# M628A.net
KiCad netlist of a schematic drawn in EAGLE
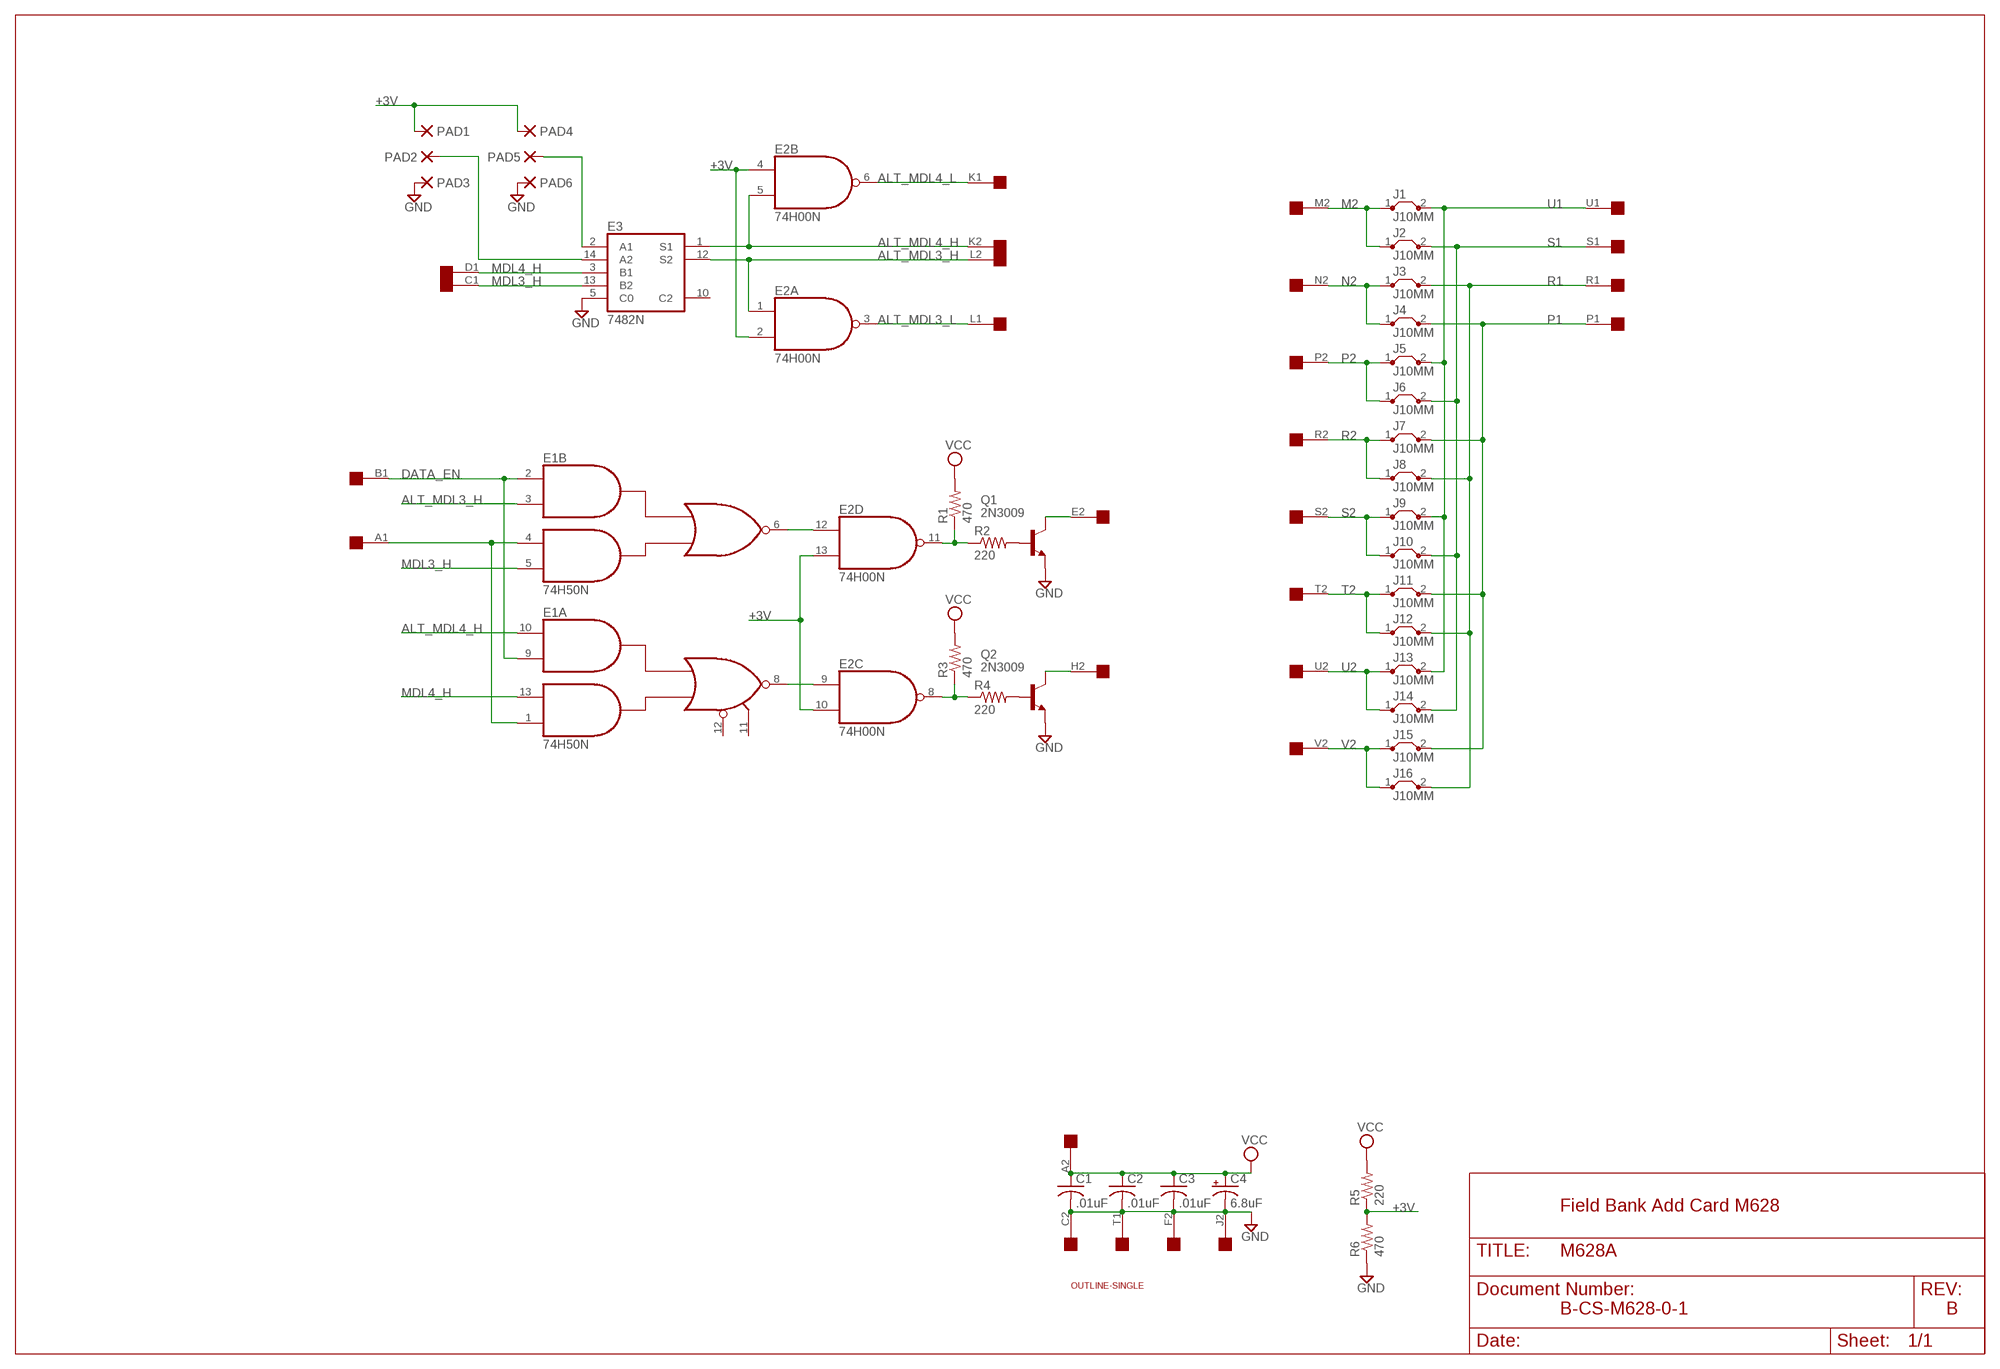
[diagram p0: schematic, sheet 1]

(export (version "E")
  (design (tool "Eeschema 10.0.6"))
  (components
    (comp (ref "C1")
      (value ".01uF")
      (footprint "eagle-import:C050-025X075")
      (libsource (lib "eagle-import") (part "C-US050-025X075"))
    )
    (comp (ref "C2")
      (value ".01uF")
      (footprint "eagle-import:C050-025X075")
      (libsource (lib "eagle-import") (part "C-US050-025X075"))
    )
    (comp (ref "C3")
      (value ".01uF")
      (footprint "eagle-import:C050-025X075")
      (libsource (lib "eagle-import") (part "C-US050-025X075"))
    )
    (comp (ref "C4")
      (value "6.8uF")
      (footprint "eagle-import:E12-8")
      (libsource (lib "eagle-import") (part "CPOL-USE20-8AXIAL"))
    )
    (comp (ref "E1")
      (value "74H50N")
      (footprint "eagle-import:DIL14")
      (libsource (lib "eagle-import") (part "7450N"))
    )
    (comp (ref "E2")
      (value "74H00N")
      (footprint "eagle-import:DIL14")
      (libsource (lib "eagle-import") (part "7400N"))
    )
    (comp (ref "E3")
      (value "7482N")
      (footprint "eagle-import:DIL14")
      (libsource (lib "eagle-import") (part "7482N"))
    )
    (comp (ref "J1")
      (value "J10MM")
      (footprint "eagle-import:10")
      (libsource (lib "eagle-import") (part "J10MM"))
    )
    (comp (ref "J2")
      (value "J10MM")
      (footprint "eagle-import:10")
      (libsource (lib "eagle-import") (part "J10MM"))
    )
    (comp (ref "J3")
      (value "J10MM")
      (footprint "eagle-import:10")
      (libsource (lib "eagle-import") (part "J10MM"))
    )
    (comp (ref "J4")
      (value "J10MM")
      (footprint "eagle-import:10")
      (libsource (lib "eagle-import") (part "J10MM"))
    )
    (comp (ref "J5")
      (value "J10MM")
      (footprint "eagle-import:10")
      (libsource (lib "eagle-import") (part "J10MM"))
    )
    (comp (ref "J6")
      (value "J10MM")
      (footprint "eagle-import:10")
      (libsource (lib "eagle-import") (part "J10MM"))
    )
    (comp (ref "J7")
      (value "J10MM")
      (footprint "eagle-import:10")
      (libsource (lib "eagle-import") (part "J10MM"))
    )
    (comp (ref "J8")
      (value "J10MM")
      (footprint "eagle-import:10")
      (libsource (lib "eagle-import") (part "J10MM"))
    )
    (comp (ref "J9")
      (value "J10MM")
      (footprint "eagle-import:10")
      (libsource (lib "eagle-import") (part "J10MM"))
    )
    (comp (ref "J10")
      (value "J10MM")
      (footprint "eagle-import:10")
      (libsource (lib "eagle-import") (part "J10MM"))
    )
    (comp (ref "J11")
      (value "J10MM")
      (footprint "eagle-import:10")
      (libsource (lib "eagle-import") (part "J10MM"))
    )
    (comp (ref "J12")
      (value "J10MM")
      (footprint "eagle-import:10")
      (libsource (lib "eagle-import") (part "J10MM"))
    )
    (comp (ref "J13")
      (value "J10MM")
      (footprint "eagle-import:10")
      (libsource (lib "eagle-import") (part "J10MM"))
    )
    (comp (ref "J14")
      (value "J10MM")
      (footprint "eagle-import:10")
      (libsource (lib "eagle-import") (part "J10MM"))
    )
    (comp (ref "J15")
      (value "J10MM")
      (footprint "eagle-import:10")
      (libsource (lib "eagle-import") (part "J10MM"))
    )
    (comp (ref "J16")
      (value "J10MM")
      (footprint "eagle-import:10")
      (libsource (lib "eagle-import") (part "J10MM"))
    )
    (comp (ref "PAD1")
      (value "PAD-0420")
      (footprint "eagle-import:0420")
      (libsource (lib "eagle-import") (part "PAD-0420"))
    )
    (comp (ref "PAD2")
      (value "PAD-0420")
      (footprint "eagle-import:0420")
      (libsource (lib "eagle-import") (part "PAD-0420"))
    )
    (comp (ref "PAD3")
      (value "PAD-0420")
      (footprint "eagle-import:0420")
      (libsource (lib "eagle-import") (part "PAD-0420"))
    )
    (comp (ref "PAD4")
      (value "PAD-0420")
      (footprint "eagle-import:0420")
      (libsource (lib "eagle-import") (part "PAD-0420"))
    )
    (comp (ref "PAD5")
      (value "PAD-0420")
      (footprint "eagle-import:0420")
      (libsource (lib "eagle-import") (part "PAD-0420"))
    )
    (comp (ref "PAD6")
      (value "PAD-0420")
      (footprint "eagle-import:0420")
      (libsource (lib "eagle-import") (part "PAD-0420"))
    )
    (comp (ref "Q1")
      (value "2N3009")
      (footprint "eagle-import:TO5")
      (libsource (lib "eagle-import") (part "2N2102"))
    )
    (comp (ref "Q2")
      (value "2N3009")
      (footprint "eagle-import:TO5")
      (libsource (lib "eagle-import") (part "2N2102"))
    )
    (comp (ref "R1")
      (value "470")
      (footprint "eagle-import:0207_10")
      (libsource (lib "eagle-import") (part "R-US_0207/10"))
    )
    (comp (ref "R2")
      (value "220")
      (footprint "eagle-import:0207_10")
      (libsource (lib "eagle-import") (part "R-US_0207/10"))
    )
    (comp (ref "R3")
      (value "470")
      (footprint "eagle-import:0207_10")
      (libsource (lib "eagle-import") (part "R-US_0207/10"))
    )
    (comp (ref "R4")
      (value "220")
      (footprint "eagle-import:0207_10")
      (libsource (lib "eagle-import") (part "R-US_0207/10"))
    )
    (comp (ref "R5")
      (value "220")
      (footprint "eagle-import:0207_10")
      (libsource (lib "eagle-import") (part "R-US_0207/10"))
    )
    (comp (ref "R6")
      (value "470")
      (footprint "eagle-import:0207_10")
      (libsource (lib "eagle-import") (part "R-US_0207/10"))
    )
    (comp (ref "U$1")
      (value "OUTLINE-SINGLE")
      (footprint "eagle-import:SINGLE")
      (libsource (lib "eagle-import") (part "OUTLINE-SINGLE"))
    )
    (comp (ref "U$2")
      (value "SINGLE")
      (footprint "eagle-import:EDGE-CON2")
      (libsource (lib "eagle-import") (part "SINGLE"))
    )
  )
  (nets
    (net (code "1") (name "/+3V") (class "Default")
      (node (ref "E2") (pin "10") (pinfunction "I1_10") (pintype "input"))
      (node (ref "E2") (pin "13") (pinfunction "I1_13") (pintype "input"))
      (node (ref "E2") (pin "2") (pinfunction "I1_2") (pintype "input"))
      (node (ref "E2") (pin "4") (pinfunction "I0_4") (pintype "input"))
      (node (ref "PAD1") (pin "P$1") (pinfunction "P_P$1") (pintype "passive"))
      (node (ref "PAD4") (pin "P$1") (pinfunction "P_P$1") (pintype "passive"))
      (node (ref "R5") (pin "1") (pinfunction "1_1") (pintype "passive"))
      (node (ref "R6") (pin "2") (pinfunction "2_2") (pintype "passive"))
    )
    (net (code "2") (name "/ALT_MDL3_H") (class "Default")
      (node (ref "E1") (pin "3") (pinfunction "I2_3") (pintype "input"))
      (node (ref "E2") (pin "1") (pinfunction "I0_1") (pintype "input"))
      (node (ref "E3") (pin "12") (pinfunction "S2_12") (pintype "output"))
      (node (ref "U$2") (pin "L2") (pinfunction "1_L2") (pintype "bidirectional"))
    )
    (net (code "3") (name "/ALT_MDL3_L") (class "Default")
      (node (ref "E2") (pin "3") (pinfunction "O_3") (pintype "output"))
      (node (ref "U$2") (pin "L1") (pinfunction "1_L1") (pintype "bidirectional"))
    )
    (net (code "4") (name "/ALT_MDL4_H") (class "Default")
      (node (ref "E1") (pin "10") (pinfunction "I1_10") (pintype "input"))
      (node (ref "E2") (pin "5") (pinfunction "I1_5") (pintype "input"))
      (node (ref "E3") (pin "1") (pinfunction "S1_1") (pintype "output"))
      (node (ref "U$2") (pin "K2") (pinfunction "1_K2") (pintype "bidirectional"))
    )
    (net (code "5") (name "/ALT_MDL4_L") (class "Default")
      (node (ref "E2") (pin "6") (pinfunction "O_6") (pintype "output"))
      (node (ref "U$2") (pin "K1") (pinfunction "1_K1") (pintype "bidirectional"))
    )
    (net (code "6") (name "/DATA_EN") (class "Default")
      (node (ref "E1") (pin "2") (pinfunction "I1_2") (pintype "input"))
      (node (ref "E1") (pin "9") (pinfunction "I2_9") (pintype "input"))
      (node (ref "U$2") (pin "B1") (pinfunction "1_B1") (pintype "bidirectional"))
    )
    (net (code "7") (name "/M2") (class "Default")
      (node (ref "J1") (pin "1") (pinfunction "1_1") (pintype "passive"))
      (node (ref "J2") (pin "1") (pinfunction "1_1") (pintype "passive"))
      (node (ref "U$2") (pin "M2") (pinfunction "1_M2") (pintype "bidirectional"))
    )
    (net (code "8") (name "/MDL3_H") (class "Default")
      (node (ref "E1") (pin "5") (pinfunction "I4_5") (pintype "input"))
      (node (ref "E3") (pin "13") (pinfunction "B2_13") (pintype "input"))
      (node (ref "U$2") (pin "C1") (pinfunction "1_C1") (pintype "bidirectional"))
    )
    (net (code "9") (name "/MDL4_H") (class "Default")
      (node (ref "E1") (pin "13") (pinfunction "I3_13") (pintype "input"))
      (node (ref "E3") (pin "3") (pinfunction "B1_3") (pintype "input"))
      (node (ref "U$2") (pin "D1") (pinfunction "1_D1") (pintype "bidirectional"))
    )
    (net (code "10") (name "/N2") (class "Default")
      (node (ref "J3") (pin "1") (pinfunction "1_1") (pintype "passive"))
      (node (ref "J4") (pin "1") (pinfunction "1_1") (pintype "passive"))
      (node (ref "U$2") (pin "N2") (pinfunction "1_N2") (pintype "bidirectional"))
    )
    (net (code "11") (name "/P1") (class "Default")
      (node (ref "J11") (pin "2") (pinfunction "2_2") (pintype "passive"))
      (node (ref "J15") (pin "2") (pinfunction "2_2") (pintype "passive"))
      (node (ref "J4") (pin "2") (pinfunction "2_2") (pintype "passive"))
      (node (ref "J7") (pin "2") (pinfunction "2_2") (pintype "passive"))
      (node (ref "U$2") (pin "P1") (pinfunction "1_P1") (pintype "bidirectional"))
    )
    (net (code "12") (name "/P2") (class "Default")
      (node (ref "J5") (pin "1") (pinfunction "1_1") (pintype "passive"))
      (node (ref "J6") (pin "1") (pinfunction "1_1") (pintype "passive"))
      (node (ref "U$2") (pin "P2") (pinfunction "1_P2") (pintype "bidirectional"))
    )
    (net (code "13") (name "/R1") (class "Default")
      (node (ref "J12") (pin "2") (pinfunction "2_2") (pintype "passive"))
      (node (ref "J16") (pin "2") (pinfunction "2_2") (pintype "passive"))
      (node (ref "J3") (pin "2") (pinfunction "2_2") (pintype "passive"))
      (node (ref "J8") (pin "2") (pinfunction "2_2") (pintype "passive"))
      (node (ref "U$2") (pin "R1") (pinfunction "1_R1") (pintype "bidirectional"))
    )
    (net (code "14") (name "/R2") (class "Default")
      (node (ref "J7") (pin "1") (pinfunction "1_1") (pintype "passive"))
      (node (ref "J8") (pin "1") (pinfunction "1_1") (pintype "passive"))
      (node (ref "U$2") (pin "R2") (pinfunction "1_R2") (pintype "bidirectional"))
    )
    (net (code "15") (name "/S1") (class "Default")
      (node (ref "J10") (pin "2") (pinfunction "2_2") (pintype "passive"))
      (node (ref "J14") (pin "2") (pinfunction "2_2") (pintype "passive"))
      (node (ref "J2") (pin "2") (pinfunction "2_2") (pintype "passive"))
      (node (ref "J6") (pin "2") (pinfunction "2_2") (pintype "passive"))
      (node (ref "U$2") (pin "S1") (pinfunction "1_S1") (pintype "bidirectional"))
    )
    (net (code "16") (name "/S2") (class "Default")
      (node (ref "J10") (pin "1") (pinfunction "1_1") (pintype "passive"))
      (node (ref "J9") (pin "1") (pinfunction "1_1") (pintype "passive"))
      (node (ref "U$2") (pin "S2") (pinfunction "1_S2") (pintype "bidirectional"))
    )
    (net (code "17") (name "/T2") (class "Default")
      (node (ref "J11") (pin "1") (pinfunction "1_1") (pintype "passive"))
      (node (ref "J12") (pin "1") (pinfunction "1_1") (pintype "passive"))
      (node (ref "U$2") (pin "T2") (pinfunction "1_T2") (pintype "bidirectional"))
    )
    (net (code "18") (name "/U1") (class "Default")
      (node (ref "J1") (pin "2") (pinfunction "2_2") (pintype "passive"))
      (node (ref "J13") (pin "2") (pinfunction "2_2") (pintype "passive"))
      (node (ref "J5") (pin "2") (pinfunction "2_2") (pintype "passive"))
      (node (ref "J9") (pin "2") (pinfunction "2_2") (pintype "passive"))
      (node (ref "U$2") (pin "U1") (pinfunction "1_U1") (pintype "bidirectional"))
    )
    (net (code "19") (name "/U2") (class "Default")
      (node (ref "J13") (pin "1") (pinfunction "1_1") (pintype "passive"))
      (node (ref "J14") (pin "1") (pinfunction "1_1") (pintype "passive"))
      (node (ref "U$2") (pin "U2") (pinfunction "1_U2") (pintype "bidirectional"))
    )
    (net (code "20") (name "/V2") (class "Default")
      (node (ref "J15") (pin "1") (pinfunction "1_1") (pintype "passive"))
      (node (ref "J16") (pin "1") (pinfunction "1_1") (pintype "passive"))
      (node (ref "U$2") (pin "V2") (pinfunction "1_V2") (pintype "bidirectional"))
    )
    (net (code "21") (name "GND") (class "Default")
      (node (ref "C1") (pin "2") (pinfunction "2_2") (pintype "passive"))
      (node (ref "C2") (pin "2") (pinfunction "2_2") (pintype "passive"))
      (node (ref "C3") (pin "2") (pinfunction "2_2") (pintype "passive"))
      (node (ref "C4") (pin "-") (pinfunction "-_-") (pintype "passive"))
      (node (ref "E3") (pin "5") (pinfunction "C0_5") (pintype "input"))
      (node (ref "PAD3") (pin "P$1") (pinfunction "P_P$1") (pintype "passive"))
      (node (ref "PAD6") (pin "P$1") (pinfunction "P_P$1") (pintype "passive"))
      (node (ref "Q1") (pin "1") (pinfunction "E_1") (pintype "passive"))
      (node (ref "Q2") (pin "1") (pinfunction "E_1") (pintype "passive"))
      (node (ref "R6") (pin "1") (pinfunction "1_1") (pintype "passive"))
      (node (ref "U$2") (pin "C2") (pinfunction "1_C2") (pintype "bidirectional"))
      (node (ref "U$2") (pin "F2") (pinfunction "1_F2") (pintype "bidirectional"))
      (node (ref "U$2") (pin "J2") (pinfunction "1_J2") (pintype "bidirectional"))
      (node (ref "U$2") (pin "T1") (pinfunction "1_T1") (pintype "bidirectional"))
    )
    (net (code "22") (name "Net-(E1A-I4)") (class "Default")
      (node (ref "E1") (pin "1") (pinfunction "I4_1") (pintype "input"))
      (node (ref "E1") (pin "4") (pinfunction "I3_4") (pintype "input"))
      (node (ref "U$2") (pin "A1") (pinfunction "1_A1") (pintype "bidirectional"))
    )
    (net (code "23") (name "Net-(E1A-O)") (class "Default")
      (node (ref "E1") (pin "8") (pinfunction "O_8") (pintype "output"))
      (node (ref "E2") (pin "9") (pinfunction "I0_9") (pintype "input"))
    )
    (net (code "24") (name "Net-(E1B-O)") (class "Default")
      (node (ref "E1") (pin "6") (pinfunction "O_6") (pintype "output"))
      (node (ref "E2") (pin "12") (pinfunction "I0_12") (pintype "input"))
    )
    (net (code "25") (name "Net-(E2C-O)") (class "Default")
      (node (ref "E2") (pin "8") (pinfunction "O_8") (pintype "output"))
      (node (ref "R3") (pin "1") (pinfunction "1_1") (pintype "passive"))
      (node (ref "R4") (pin "1") (pinfunction "1_1") (pintype "passive"))
    )
    (net (code "26") (name "Net-(E2D-O)") (class "Default")
      (node (ref "E2") (pin "11") (pinfunction "O_11") (pintype "output"))
      (node (ref "R1") (pin "1") (pinfunction "1_1") (pintype "passive"))
      (node (ref "R2") (pin "1") (pinfunction "1_1") (pintype "passive"))
    )
    (net (code "27") (name "Net-(E3E-A1)") (class "Default")
      (node (ref "E3") (pin "2") (pinfunction "A1_2") (pintype "input"))
      (node (ref "PAD5") (pin "P$1") (pinfunction "P_P$1") (pintype "passive"))
    )
    (net (code "28") (name "Net-(E3E-A2)") (class "Default")
      (node (ref "E3") (pin "14") (pinfunction "A2_14") (pintype "input"))
      (node (ref "PAD2") (pin "P$1") (pinfunction "P_P$1") (pintype "passive"))
    )
    (net (code "29") (name "Net-(Q1-B)") (class "Default")
      (node (ref "Q1") (pin "2") (pinfunction "B_2") (pintype "passive"))
      (node (ref "R2") (pin "2") (pinfunction "2_2") (pintype "passive"))
    )
    (net (code "30") (name "Net-(Q1-C)") (class "Default")
      (node (ref "Q1") (pin "3") (pinfunction "C_3") (pintype "passive"))
      (node (ref "U$2") (pin "E2") (pinfunction "1_E2") (pintype "bidirectional"))
    )
    (net (code "31") (name "Net-(Q2-B)") (class "Default")
      (node (ref "Q2") (pin "2") (pinfunction "B_2") (pintype "passive"))
      (node (ref "R4") (pin "2") (pinfunction "2_2") (pintype "passive"))
    )
    (net (code "32") (name "Net-(Q2-C)") (class "Default")
      (node (ref "Q2") (pin "3") (pinfunction "C_3") (pintype "passive"))
      (node (ref "U$2") (pin "H2") (pinfunction "1_H2") (pintype "bidirectional"))
    )
    (net (code "33") (name "VCC") (class "Default")
      (node (ref "C1") (pin "1") (pinfunction "1_1") (pintype "passive"))
      (node (ref "C2") (pin "1") (pinfunction "1_1") (pintype "passive"))
      (node (ref "C3") (pin "1") (pinfunction "1_1") (pintype "passive"))
      (node (ref "C4") (pin "+") (pinfunction "+_+") (pintype "passive"))
      (node (ref "R1") (pin "2") (pinfunction "2_2") (pintype "passive"))
      (node (ref "R3") (pin "2") (pinfunction "2_2") (pintype "passive"))
      (node (ref "R5") (pin "2") (pinfunction "2_2") (pintype "passive"))
      (node (ref "U$2") (pin "A2") (pinfunction "1_A2") (pintype "bidirectional"))
    )
    (net (code "34") (name "unconnected-(E1A-I5-Pad12)") (class "Default")
      (node (ref "E1") (pin "12") (pinfunction "I5_12") (pintype "passive"))
    )
    (net (code "35") (name "unconnected-(E1A-I6-Pad11)") (class "Default")
      (node (ref "E1") (pin "11") (pinfunction "I6_11") (pintype "passive"))
    )
    (net (code "36") (name "unconnected-(E3E-C2-Pad10)") (class "Default")
      (node (ref "E3") (pin "10") (pinfunction "C2_10") (pintype "output"))
    )
  )
)
